# Main.net
KiCad netlist of a schematic drawn in Altium Designer
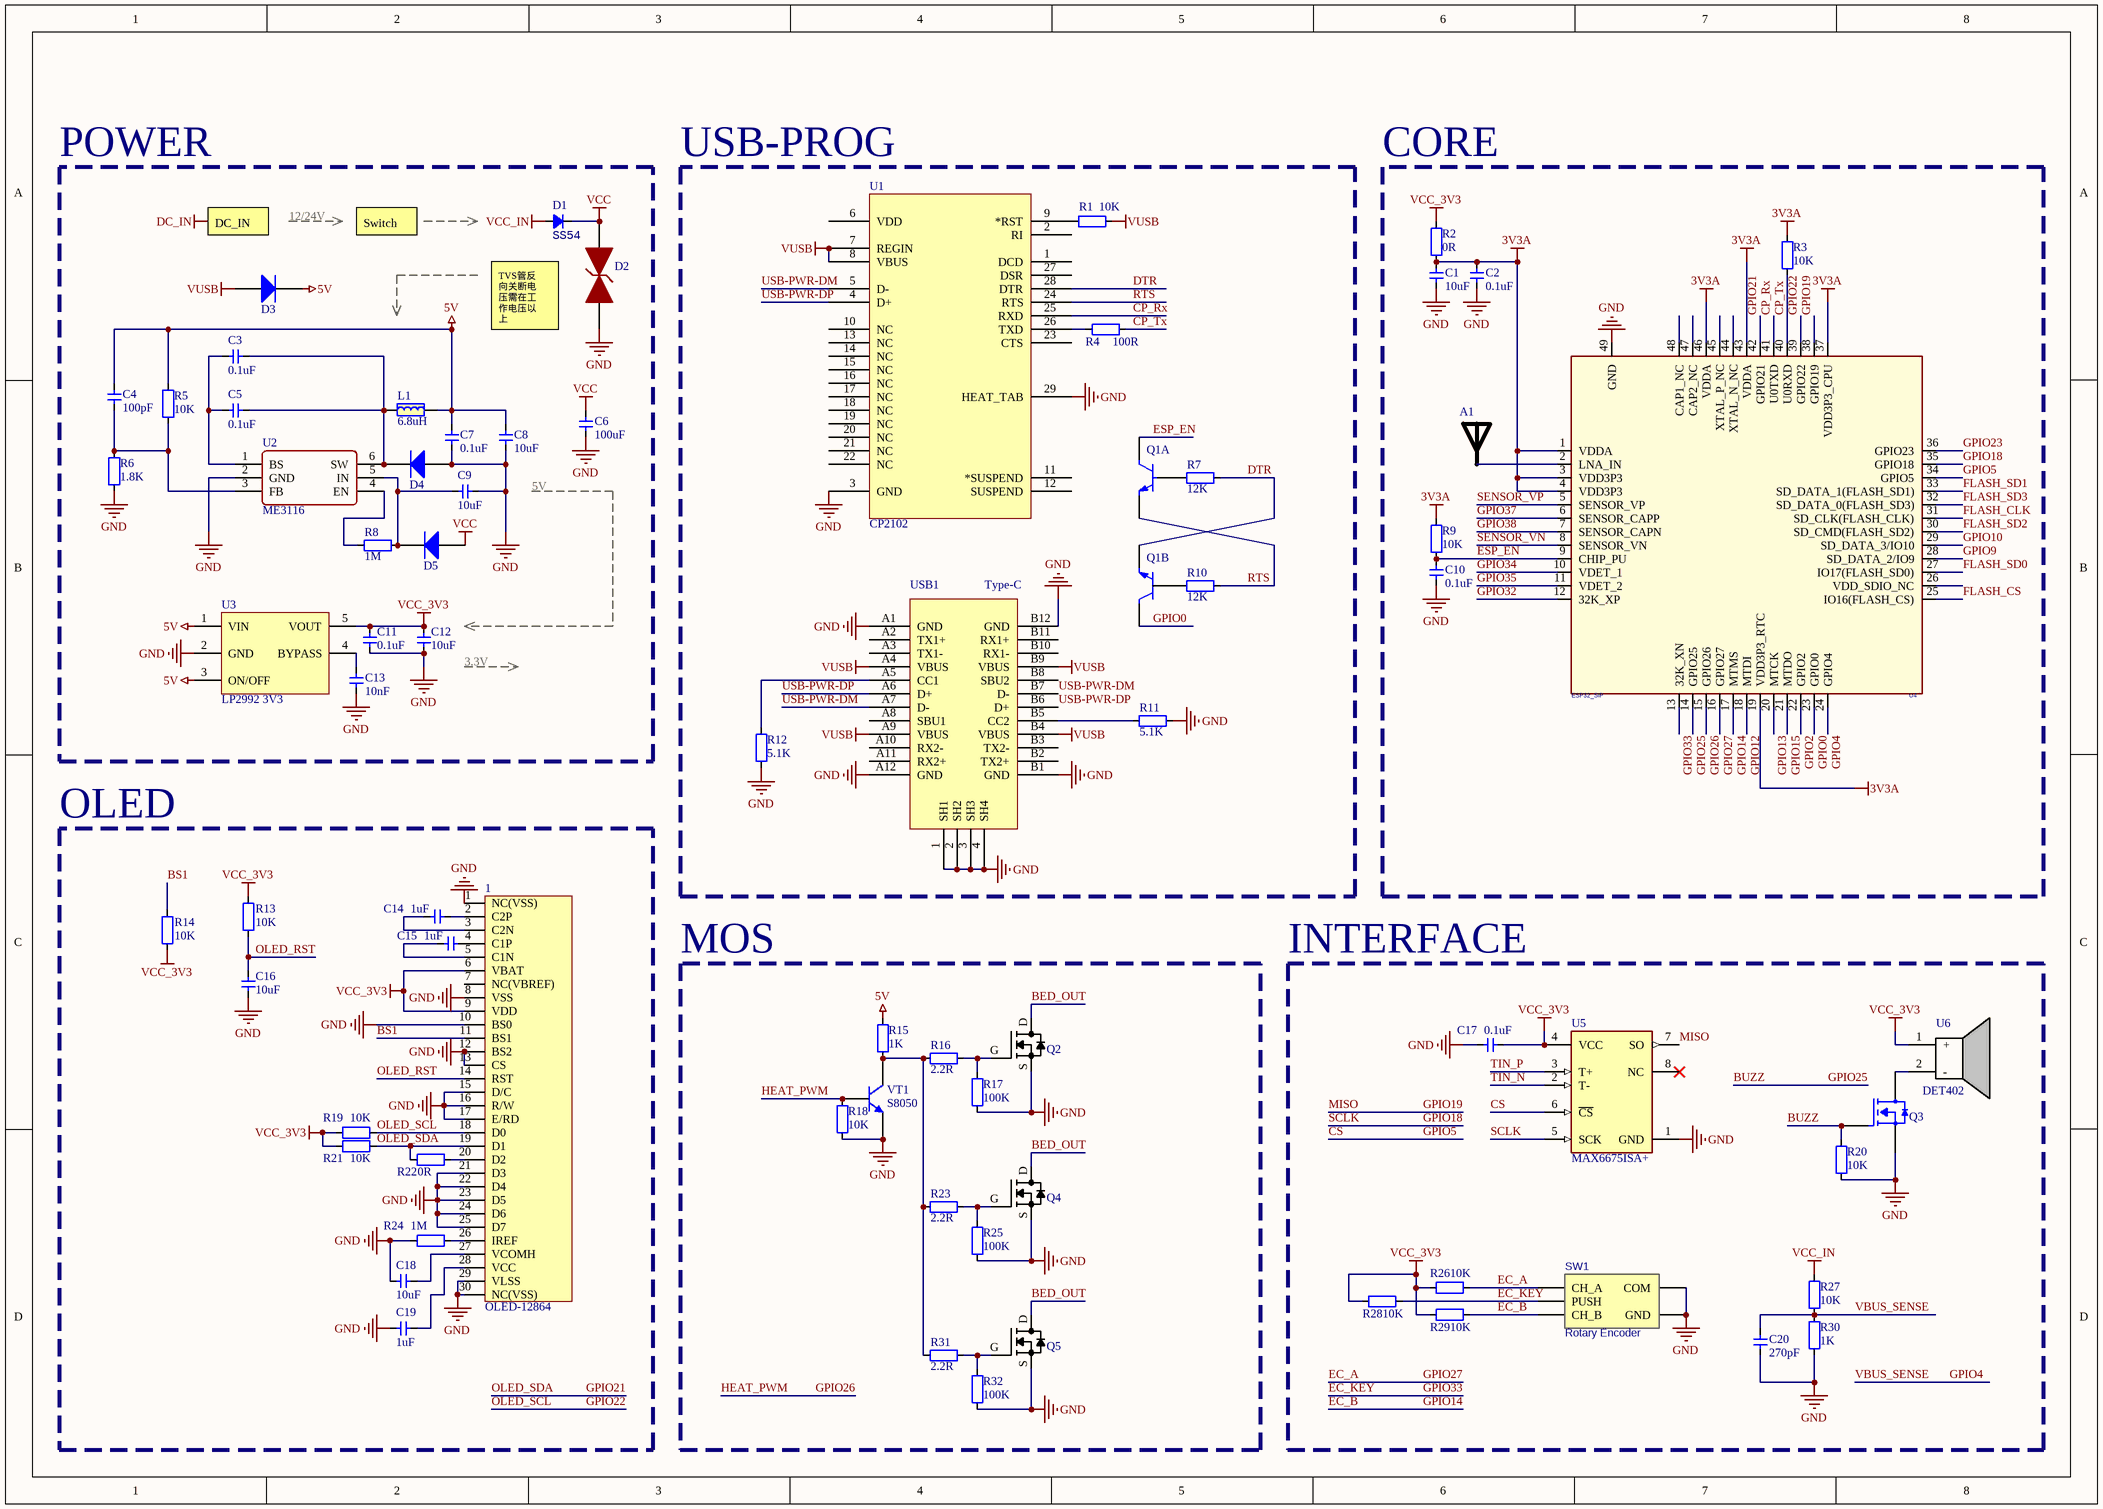
[diagram p0: Main.SchDoc]

(export (version "E")
  (design (tool "Eeschema 10.0.6"))
  (components
    (comp (ref "1")
      (value "OLED-12864")
      (footprint "OLED-12864-1.3-TOP")
      (description "显示屏")
      (libsource (lib "MyPcbLib") (part "OLED-12864"))
    )
    (comp (ref "A1")
      (value "RAINSUN")
      (footprint "ANT-Rainsun-AN5120")
      (libsource (lib "MyPcbLib") (part "ANT-Rainsun-AP5120"))
    )
    (comp (ref "C1")
      (value "10uF")
      (footprint "CAP_0402")
      (description "Capacitor")
      (libsource (lib "MyPcbLib") (part "电容-0402"))
    )
    (comp (ref "C2")
      (value "0.1uF")
      (footprint "CAP_0402")
      (description "Capacitor")
      (libsource (lib "MyPcbLib") (part "电容-0402"))
    )
    (comp (ref "C3")
      (value "0.1uF")
      (footprint "CAP_0402")
      (description "Capacitor")
      (libsource (lib "MyPcbLib") (part "电容-0402"))
    )
    (comp (ref "C4")
      (value "100pF")
      (footprint "CAP_0402")
      (description "Capacitor")
      (libsource (lib "MyPcbLib") (part "电容-0402"))
    )
    (comp (ref "C5")
      (value "0.1uF")
      (footprint "CAP_0402")
      (description "Capacitor")
      (libsource (lib "MyPcbLib") (part "电容-0402"))
    )
    (comp (ref "C6")
      (value "100uF")
      (footprint "1206-CAP")
      (description "Capacitor")
      (libsource (lib "MyPcbLib") (part "电容-1206"))
    )
    (comp (ref "C7")
      (value "0.1uF")
      (footprint "CAP_0402")
      (description "Capacitor")
      (libsource (lib "MyPcbLib") (part "电容-0402"))
    )
    (comp (ref "C8")
      (value "10uF")
      (footprint "CAP_0402")
      (description "Capacitor")
      (libsource (lib "MyPcbLib") (part "电容-0402"))
    )
    (comp (ref "C9")
      (value "10uF")
      (footprint "CAP_0402")
      (description "Capacitor")
      (libsource (lib "MyPcbLib") (part "电容-0402"))
    )
    (comp (ref "C10")
      (value "0.1uF")
      (footprint "CAP_0402")
      (description "Capacitor")
      (libsource (lib "MyPcbLib") (part "电容-0402"))
    )
    (comp (ref "C11")
      (value "0.1uF")
      (footprint "CAP_0402")
      (description "Capacitor")
      (libsource (lib "MyPcbLib") (part "电容-0402"))
    )
    (comp (ref "C12")
      (value "10uF")
      (footprint "CAP_0402")
      (description "Capacitor")
      (libsource (lib "MyPcbLib") (part "电容-0402"))
    )
    (comp (ref "C13")
      (value "10nF")
      (footprint "CAP_0402")
      (description "Capacitor")
      (libsource (lib "MyPcbLib") (part "电容-0402"))
    )
    (comp (ref "C14")
      (value "1uF")
      (footprint "CAP_0402")
      (description "Capacitor")
      (libsource (lib "MyPcbLib") (part "电容-0402"))
    )
    (comp (ref "C15")
      (value "1uF")
      (footprint "CAP_0402")
      (description "Capacitor")
      (libsource (lib "MyPcbLib") (part "电容-0402"))
    )
    (comp (ref "C16")
      (value "10uF")
      (footprint "CAP_0402")
      (description "Capacitor")
      (libsource (lib "MyPcbLib") (part "电容-0402"))
    )
    (comp (ref "C17")
      (value "0.1uF")
      (footprint "CAP_0402")
      (description "Capacitor")
      (libsource (lib "MyPcbLib") (part "电容-0402"))
    )
    (comp (ref "C18")
      (value "10uF")
      (footprint "CAP_0402")
      (description "Capacitor")
      (libsource (lib "MyPcbLib") (part "电容-0402"))
    )
    (comp (ref "C19")
      (value "1uF")
      (footprint "CAP_0402")
      (description "Capacitor")
      (libsource (lib "MyPcbLib") (part "电容-0402"))
    )
    (comp (ref "C20")
      (value "270pF")
      (footprint "CAP_0402")
      (description "Capacitor")
      (libsource (lib "MyPcbLib") (part "电容-0402"))
    )
    (comp (ref "D1")
      (value "SS54")
      (footprint "DO-214AC")
      (description "Diode")
      (libsource (lib "KitSprout") (part "Diode_SMA"))
    )
    (comp (ref "D2")
      (value "SMBJ28CA")
      (footprint "SMBJ-CA_MFG")
      (libsource (lib "MyPcbLib") (part "SMBJ28CA"))
    )
    (comp (ref "D3")
      (value "二极管-5819W")
      (footprint "SOD-323")
      (description "40V")
      (libsource (lib "MyPcbLib") (part "二极管-5819W"))
    )
    (comp (ref "D4")
      (value "二极管-5819W")
      (footprint "SOD-323")
      (description "40V")
      (libsource (lib "MyPcbLib") (part "二极管-5819W"))
    )
    (comp (ref "D5")
      (value "二极管-5819W")
      (footprint "SOD-323")
      (description "40V")
      (libsource (lib "MyPcbLib") (part "二极管-5819W"))
    )
    (comp (ref "L1") (value "6.8uH") (footprint "IND-201612") (libsource (lib "MyPcbLib") (part "电感-201612")))
    (comp (ref "Q1")
      (value "BC847BVC-7")
      (footprint "SOT563-6")
      (libsource (lib "MyPcbLib") (part "BC847BVC-7"))
    )
    (comp (ref "Q2")
      (value "NTMFS5C628NLT")
      (footprint "SO8FL")
      (description "MOSFET N-CH 60V SO8FL")
      (fields
        (field (name "MANUFACTURER") "ON Semiconductor")
        (field (name "MANUFACTURER PART NUMBER") "NTMFS5C628NLT1G")
      )
      (libsource (lib "MyPcbLib") (part "NTMFS5C628NLT"))
    )
    (comp (ref "Q3")
      (value "AO3400A")
      (footprint "SOT23-3")
      (description "N-MOS")
      (libsource (lib "MyPcbLib") (part "AO3400A"))
    )
    (comp (ref "Q4")
      (value "NTMFS5C628NLT")
      (footprint "SO8FL")
      (description "MOSFET N-CH 60V SO8FL")
      (fields
        (field (name "MANUFACTURER") "ON Semiconductor")
        (field (name "MANUFACTURER PART NUMBER") "NTMFS5C628NLT1G")
      )
      (libsource (lib "MyPcbLib") (part "NTMFS5C628NLT"))
    )
    (comp (ref "Q5")
      (value "NTMFS5C628NLT")
      (footprint "SO8FL")
      (description "MOSFET N-CH 60V SO8FL")
      (fields
        (field (name "MANUFACTURER") "ON Semiconductor")
        (field (name "MANUFACTURER PART NUMBER") "NTMFS5C628NLT1G")
      )
      (libsource (lib "MyPcbLib") (part "NTMFS5C628NLT"))
    )
    (comp (ref "R1")
      (value "10K")
      (footprint "RES_0402")
      (description "Resistor")
      (libsource (lib "MyPcbLib") (part "电阻-0402"))
    )
    (comp (ref "R2")
      (value "0R")
      (footprint "RES_0402")
      (description "Resistor")
      (libsource (lib "") (part "电阻-0402_1"))
    )
    (comp (ref "R3")
      (value "10K")
      (footprint "RES_0402")
      (description "Resistor")
      (libsource (lib "") (part "电阻-0402_2"))
    )
    (comp (ref "R4")
      (value "100R")
      (footprint "RES_0402")
      (description "Resistor")
      (libsource (lib "MyPcbLib") (part "电阻-0402"))
    )
    (comp (ref "R5")
      (value "10K")
      (footprint "RES_0402")
      (description "Resistor")
      (libsource (lib "") (part "电阻-0402_2"))
    )
    (comp (ref "R6")
      (value "1.8K")
      (footprint "RES_0402")
      (description "Resistor")
      (libsource (lib "") (part "电阻-0402_2"))
    )
    (comp (ref "R7")
      (value "12K")
      (footprint "RES_0402")
      (description "Resistor")
      (libsource (lib "MyPcbLib") (part "电阻-0402"))
    )
    (comp (ref "R8")
      (value "1M")
      (footprint "RES_0402")
      (description "Resistor")
      (libsource (lib "MyPcbLib") (part "电阻-0402"))
    )
    (comp (ref "R9")
      (value "10K")
      (footprint "RES_0402")
      (description "Resistor")
      (libsource (lib "") (part "电阻-0402_1"))
    )
    (comp (ref "R10")
      (value "12K")
      (footprint "RES_0402")
      (description "Resistor")
      (libsource (lib "MyPcbLib") (part "电阻-0402"))
    )
    (comp (ref "R11")
      (value "5.1K")
      (footprint "RES_0402")
      (description "Resistor")
      (libsource (lib "MyPcbLib") (part "电阻-0402"))
    )
    (comp (ref "R12")
      (value "5.1K")
      (footprint "RES_0402")
      (description "Resistor")
      (libsource (lib "") (part "电阻-0402_1"))
    )
    (comp (ref "R13")
      (value "10K")
      (footprint "RES_0402")
      (description "Resistor")
      (libsource (lib "") (part "电阻-0402_2"))
    )
    (comp (ref "R14")
      (value "10K")
      (footprint "RES_0402")
      (description "Resistor")
      (libsource (lib "") (part "电阻-0402_2"))
    )
    (comp (ref "R15")
      (value "1K")
      (footprint "RES_0402")
      (description "Resistor")
      (libsource (lib "") (part "电阻-0402_2"))
    )
    (comp (ref "R16")
      (value "2.2R")
      (footprint "RES_0402")
      (description "Resistor")
      (libsource (lib "MyPcbLib") (part "电阻-0402"))
    )
    (comp (ref "R17")
      (value "100K")
      (footprint "RES_0402")
      (description "Resistor")
      (libsource (lib "") (part "电阻-0402_1"))
    )
    (comp (ref "R18")
      (value "10K")
      (footprint "RES_0402")
      (description "Resistor")
      (libsource (lib "") (part "电阻-0402_1"))
    )
    (comp (ref "R19")
      (value "10K")
      (footprint "RES_0402")
      (description "Resistor")
      (libsource (lib "") (part "电阻-0402_3"))
    )
    (comp (ref "R20")
      (value "10K")
      (footprint "RES_0402")
      (description "Resistor")
      (libsource (lib "") (part "电阻-0402_2"))
    )
    (comp (ref "R21")
      (value "10K")
      (footprint "RES_0402")
      (description "Resistor")
      (libsource (lib "") (part "电阻-0402_3"))
    )
    (comp (ref "R22")
      (value "0R")
      (footprint "RES_0402")
      (description "Resistor")
      (libsource (lib "MyPcbLib") (part "电阻-0402"))
    )
    (comp (ref "R23")
      (value "2.2R")
      (footprint "RES_0402")
      (description "Resistor")
      (libsource (lib "MyPcbLib") (part "电阻-0402"))
    )
    (comp (ref "R24")
      (value "1M")
      (footprint "RES_0402")
      (description "Resistor")
      (libsource (lib "") (part "电阻-0402_3"))
    )
    (comp (ref "R25")
      (value "100K")
      (footprint "RES_0402")
      (description "Resistor")
      (libsource (lib "") (part "电阻-0402_1"))
    )
    (comp (ref "R26")
      (value "10K")
      (footprint "RES_0402")
      (description "Resistor")
      (libsource (lib "MyPcbLib") (part "电阻-0402"))
    )
    (comp (ref "R27")
      (value "10K")
      (footprint "RES_0402")
      (description "Resistor")
      (libsource (lib "") (part "电阻-0402_1"))
    )
    (comp (ref "R28")
      (value "10K")
      (footprint "RES_0402")
      (description "Resistor")
      (libsource (lib "MyPcbLib") (part "电阻-0402"))
    )
    (comp (ref "R29")
      (value "10K")
      (footprint "RES_0402")
      (description "Resistor")
      (libsource (lib "MyPcbLib") (part "电阻-0402"))
    )
    (comp (ref "R30")
      (value "1K")
      (footprint "RES_0402")
      (description "Resistor")
      (libsource (lib "") (part "电阻-0402_1"))
    )
    (comp (ref "R31")
      (value "2.2R")
      (footprint "RES_0402")
      (description "Resistor")
      (libsource (lib "MyPcbLib") (part "电阻-0402"))
    )
    (comp (ref "R32")
      (value "100K")
      (footprint "RES_0402")
      (description "Resistor")
      (libsource (lib "") (part "电阻-0402_1"))
    )
    (comp (ref "SW1")
      (value "Rotary Encoder")
      (footprint "SIQ-02FVS3")
      (fields
        (field (name "BOM_SUPPLIER PART") "C1322543")
        (field (name "BOM_MANUFACTURER PART") "EC11E1534443")
        (field (name "CONTRIBUTOR") "LCSC")
      )
      (libsource (lib "MyPcbLib") (part "Rotary Encoder"))
    )
    (comp (ref "U1")
      (value "CP2102")
      (footprint "QFN-28")
      (description "USB转TTL")
      (libsource (lib "mLib") (part "CP2102"))
    )
    (comp (ref "U2")
      (value "ME3116")
      (footprint "SOT23-6")
      (description "DC-DC")
      (libsource (lib "MyPcbLib") (part "ME3116"))
    )
    (comp (ref "U3")
      (value "LP2992 3V3")
      (footprint "SOT23-5")
      (description "LDO")
      (libsource (lib "mLib") (part "LP2992"))
    )
    (comp (ref "U4")
      (value "ESP32_SIP")
      (footprint "QFN-48_7X7")
      (libsource (lib "mLib") (part "ESP32-PICO"))
    )
    (comp (ref "U5")
      (value "MAX6675ISA")
      (footprint "SO-8")
      (description "IC THERMOCOUP TO DGTL 8-SOIC")
      (fields
        (field (name "MANUFACTURER") "Maxim Electronics")
        (field (name "OCTOPART PART NUMBER") "33bcfab92ad8ec7b")
        (field (name "PART NUMBER") "MAX6675ISA+")
      )
      (libsource (lib "MyPcbLib") (part "MAX6675ISA"))
    )
    (comp (ref "U6") (value "DET402") (footprint "DET402") (libsource (lib "MyPcbLib") (part "DET402")))
    (comp (ref "USB1")
      (value "Type-C")
      (footprint "Type-C-TOP")
      (libsource (lib "MyPcbLib") (part "USB-Type-C-TOP"))
    )
    (comp (ref "VT1")
      (value "S8050")
      (footprint "SMT_TRIODE_NPN")
      (description "Surface mount NPN transistor, package SOT-23")
      (libsource (lib "MyPcbLib") (part "SMT_TRIODE_NPN"))
    )
  )
  (nets
    (net (code "1") (name "/BED_OUT") (class "Default")
      (node (ref "Q2") (pin "D") (pinfunction "D_D") (pintype "passive"))
      (node (ref "Q4") (pin "D") (pinfunction "D_D") (pintype "passive"))
      (node (ref "Q5") (pin "D") (pinfunction "D_D") (pintype "passive"))
    )
    (net (code "2") (name "/BS1") (class "Default")
      (node (ref "1") (pin "11") (pinfunction "BS1_11") (pintype "passive"))
      (node (ref "R14") (pin "2") (pinfunction "2_2") (pintype "passive"))
    )
    (net (code "3") (name "/BUZZ") (class "Default")
      (node (ref "Q3") (pin "1") (pinfunction "G_1") (pintype "passive"))
      (node (ref "R20") (pin "2") (pinfunction "2_2") (pintype "passive"))
      (node (ref "U4") (pin "14") (pinfunction "GPIO25_14") (pintype "passive"))
    )
    (net (code "4") (name "/CP_Rx") (class "Default")
      (node (ref "U1") (pin "25") (pinfunction "RXD_25") (pintype "passive"))
      (node (ref "U4") (pin "41") (pinfunction "U0TXD_41") (pintype "power_in"))
    )
    (net (code "5") (name "/CP_Tx") (class "Default")
      (node (ref "R3") (pin "1") (pinfunction "1_1") (pintype "passive"))
      (node (ref "R4") (pin "1") (pinfunction "1_1") (pintype "passive"))
      (node (ref "U4") (pin "40") (pinfunction "U0RXD_40") (pintype "power_in"))
    )
    (net (code "6") (name "/CS") (class "Default")
      (node (ref "U4") (pin "34") (pinfunction "GPIO5_34") (pintype "passive"))
      (node (ref "U5") (pin "6") (pinfunction "~{CS}_6") (pintype "input"))
    )
    (net (code "7") (name "/DTR") (class "Default")
      (node (ref "Q1") (pin "4") (pinfunction "E2_4") (pintype "passive"))
      (node (ref "R7") (pin "1") (pinfunction "1_1") (pintype "passive"))
      (node (ref "U1") (pin "28") (pinfunction "DTR_28") (pintype "passive"))
    )
    (net (code "8") (name "/EC_A") (class "Default")
      (node (ref "R26") (pin "1") (pinfunction "1_1") (pintype "passive"))
      (node (ref "SW1") (pin "1") (pinfunction "CH_A_1") (pintype "passive"))
      (node (ref "U4") (pin "16") (pinfunction "GPIO27_16") (pintype "passive"))
    )
    (net (code "9") (name "/EC_B") (class "Default")
      (node (ref "R29") (pin "1") (pinfunction "1_1") (pintype "passive"))
      (node (ref "SW1") (pin "4") (pinfunction "CH_B_4") (pintype "passive"))
      (node (ref "U4") (pin "17") (pinfunction "MTMS_17") (pintype "passive"))
    )
    (net (code "10") (name "/EC_KEY") (class "Default")
      (node (ref "R28") (pin "1") (pinfunction "1_1") (pintype "passive"))
      (node (ref "SW1") (pin "2") (pinfunction "PUSH_2") (pintype "passive"))
      (node (ref "U4") (pin "13") (pinfunction "32K_XN_13") (pintype "passive"))
    )
    (net (code "11") (name "/ESP_EN") (class "Default")
      (node (ref "C10") (pin "1") (pinfunction "1_1") (pintype "passive"))
      (node (ref "Q1") (pin "6") (pinfunction "C1_6") (pintype "passive"))
      (node (ref "R9") (pin "2") (pinfunction "2_2") (pintype "passive"))
      (node (ref "U4") (pin "9") (pinfunction "CHIP_PU_9") (pintype "passive"))
    )
    (net (code "12") (name "/FLASH_CLK") (class "Default")
      (node (ref "U4") (pin "31") (pinfunction "SD_CLK(FLASH_CLK)_31") (pintype "passive"))
    )
    (net (code "13") (name "/FLASH_CS") (class "Default")
      (node (ref "U4") (pin "25") (pinfunction "IO16(FLASH_CS)_25") (pintype "passive"))
    )
    (net (code "14") (name "/FLASH_SD0") (class "Default")
      (node (ref "U4") (pin "27") (pinfunction "IO17(FLASH_SD0)_27") (pintype "passive"))
    )
    (net (code "15") (name "/FLASH_SD1") (class "Default")
      (node (ref "U4") (pin "33") (pinfunction "SD_DATA_1(FLASH_SD1)_33") (pintype "passive"))
    )
    (net (code "16") (name "/FLASH_SD2") (class "Default")
      (node (ref "U4") (pin "30") (pinfunction "SD_CMD(FLASH_SD2)_30") (pintype "passive"))
    )
    (net (code "17") (name "/FLASH_SD3") (class "Default")
      (node (ref "U4") (pin "32") (pinfunction "SD_DATA_0(FLASH_SD3)_32") (pintype "passive"))
    )
    (net (code "18") (name "/GPIO0") (class "Default")
      (node (ref "Q1") (pin "3") (pinfunction "C2_3") (pintype "passive"))
      (node (ref "U4") (pin "23") (pinfunction "GPIO0_23") (pintype "passive"))
    )
    (net (code "19") (name "/GPIO2") (class "Default")
      (node (ref "U4") (pin "22") (pinfunction "GPIO2_22") (pintype "passive"))
    )
    (net (code "20") (name "/GPIO4") (class "Default")
      (node (ref "C20") (pin "2") (pinfunction "2_2") (pintype "passive"))
      (node (ref "R27") (pin "2") (pinfunction "2_2") (pintype "passive"))
      (node (ref "R30") (pin "1") (pinfunction "1_1") (pintype "passive"))
      (node (ref "U4") (pin "24") (pinfunction "GPIO4_24") (pintype "passive"))
    )
    (net (code "21") (name "/GPIO9") (class "Default")
      (node (ref "U4") (pin "28") (pinfunction "SD_DATA_2/IO9_28") (pintype "passive"))
    )
    (net (code "22") (name "/GPIO10") (class "Default")
      (node (ref "U4") (pin "29") (pinfunction "SD_DATA_3/IO10_29") (pintype "passive"))
    )
    (net (code "23") (name "/GPIO12") (class "Default")
      (node (ref "U4") (pin "18") (pinfunction "MTDI_18") (pintype "passive"))
    )
    (net (code "24") (name "/GPIO13") (class "Default")
      (node (ref "U4") (pin "20") (pinfunction "MTCK_20") (pintype "passive"))
    )
    (net (code "25") (name "/GPIO15") (class "Default")
      (node (ref "U4") (pin "21") (pinfunction "MTDO_21") (pintype "passive"))
    )
    (net (code "26") (name "/GPIO18") (class "Default")
      (node (ref "U4") (pin "35") (pinfunction "GPIO18_35") (pintype "passive"))
      (node (ref "U5") (pin "5") (pinfunction "SCK_5") (pintype "input"))
    )
    (net (code "27") (name "/GPIO19") (class "Default")
      (node (ref "U4") (pin "38") (pinfunction "GPIO19_38") (pintype "passive"))
      (node (ref "U5") (pin "7") (pinfunction "SO_7") (pintype "output"))
    )
    (net (code "28") (name "/GPIO21") (class "Default")
      (node (ref "1") (pin "19") (pinfunction "D1_19") (pintype "passive"))
      (node (ref "R21") (pin "2") (pinfunction "2_2") (pintype "passive"))
      (node (ref "R22") (pin "2") (pinfunction "2_2") (pintype "passive"))
      (node (ref "U4") (pin "42") (pinfunction "GPIO21_42") (pintype "passive"))
    )
    (net (code "29") (name "/GPIO22") (class "Default")
      (node (ref "1") (pin "18") (pinfunction "D0_18") (pintype "passive"))
      (node (ref "R19") (pin "2") (pinfunction "2_2") (pintype "passive"))
      (node (ref "U4") (pin "39") (pinfunction "GPIO22_39") (pintype "passive"))
    )
    (net (code "30") (name "/GPIO23") (class "Default")
      (node (ref "U4") (pin "36") (pinfunction "GPIO23_36") (pintype "passive"))
    )
    (net (code "31") (name "/GPIO26") (class "Default")
      (node (ref "R18") (pin "1") (pinfunction "1_1") (pintype "passive"))
      (node (ref "U4") (pin "15") (pinfunction "GPIO26_15") (pintype "passive"))
      (node (ref "VT1") (pin "1") (pinfunction "B_1") (pintype "passive"))
    )
    (net (code "32") (name "/GPIO32") (class "Default")
      (node (ref "U4") (pin "12") (pinfunction "32K_XP_12") (pintype "passive"))
    )
    (net (code "33") (name "/GPIO34") (class "Default")
      (node (ref "U4") (pin "10") (pinfunction "VDET_1_10") (pintype "passive"))
    )
    (net (code "34") (name "/GPIO35") (class "Default")
      (node (ref "U4") (pin "11") (pinfunction "VDET_2_11") (pintype "passive"))
    )
    (net (code "35") (name "/GPIO37") (class "Default")
      (node (ref "U4") (pin "6") (pinfunction "SENSOR_CAPP_6") (pintype "passive"))
    )
    (net (code "36") (name "/GPIO38") (class "Default")
      (node (ref "U4") (pin "7") (pinfunction "SENSOR_CAPN_7") (pintype "passive"))
    )
    (net (code "37") (name "/OLED_RST") (class "Default")
      (node (ref "1") (pin "14") (pinfunction "RST_14") (pintype "passive"))
      (node (ref "C16") (pin "2") (pinfunction "2_2") (pintype "passive"))
      (node (ref "R13") (pin "1") (pinfunction "1_1") (pintype "passive"))
    )
    (net (code "38") (name "/RTS") (class "Default")
      (node (ref "Q1") (pin "1") (pinfunction "E1_1") (pintype "passive"))
      (node (ref "R10") (pin "1") (pinfunction "1_1") (pintype "passive"))
      (node (ref "U1") (pin "24") (pinfunction "RTS_24") (pintype "passive"))
    )
    (net (code "39") (name "/SENSOR_VN") (class "Default")
      (node (ref "U4") (pin "8") (pinfunction "SENSOR_VN_8") (pintype "passive"))
    )
    (net (code "40") (name "/SENSOR_VP") (class "Default")
      (node (ref "U4") (pin "5") (pinfunction "SENSOR_VP_5") (pintype "passive"))
    )
    (net (code "41") (name "/TIN_N") (class "Default")
      (node (ref "U5") (pin "2") (pinfunction "T-_2") (pintype "input"))
    )
    (net (code "42") (name "/TIN_P") (class "Default")
      (node (ref "U5") (pin "3") (pinfunction "T+_3") (pintype "input"))
    )
    (net (code "43") (name "/USB-PWR-DM") (class "Default")
      (node (ref "U1") (pin "5") (pinfunction "D-_5") (pintype "passive"))
      (node (ref "USB1") (pin "A7") (pinfunction "D-_A7") (pintype "passive"))
      (node (ref "USB1") (pin "B7") (pinfunction "D-_B7") (pintype "passive"))
    )
    (net (code "44") (name "/USB-PWR-DP") (class "Default")
      (node (ref "U1") (pin "4") (pinfunction "D+_4") (pintype "passive"))
      (node (ref "USB1") (pin "A6") (pinfunction "D+_A6") (pintype "passive"))
      (node (ref "USB1") (pin "B6") (pinfunction "D+_B6") (pintype "passive"))
    )
    (net (code "45") (name "3V3A") (class "Default")
      (node (ref "C1") (pin "2") (pinfunction "2_2") (pintype "passive"))
      (node (ref "C2") (pin "2") (pinfunction "2_2") (pintype "passive"))
      (node (ref "R2") (pin "2") (pinfunction "2_2") (pintype "passive"))
      (node (ref "R3") (pin "2") (pinfunction "2_2") (pintype "passive"))
      (node (ref "R9") (pin "1") (pinfunction "1_1") (pintype "passive"))
      (node (ref "U4") (pin "1") (pinfunction "VDDA_1") (pintype "power_in"))
      (node (ref "U4") (pin "19") (pinfunction "VDD3P3_RTC_19") (pintype "power_in"))
      (node (ref "U4") (pin "3") (pinfunction "VDD3P3_3") (pintype "power_in"))
      (node (ref "U4") (pin "37") (pinfunction "VDD3P3_CPU_37") (pintype "power_in"))
      (node (ref "U4") (pin "4") (pinfunction "VDD3P3_4") (pintype "power_in"))
      (node (ref "U4") (pin "43") (pinfunction "VDDA_43") (pintype "power_in"))
      (node (ref "U4") (pin "46") (pinfunction "VDDA_46") (pintype "power_in"))
    )
    (net (code "46") (name "5V") (class "Default")
      (node (ref "C4") (pin "1") (pinfunction "1_1") (pintype "passive"))
      (node (ref "C7") (pin "2") (pinfunction "2_2") (pintype "passive"))
      (node (ref "C8") (pin "2") (pinfunction "2_2") (pintype "passive"))
      (node (ref "D3") (pin "2") (pinfunction "K_2") (pintype "passive"))
      (node (ref "L1") (pin "2") (pinfunction "2_2") (pintype "passive"))
      (node (ref "R15") (pin "2") (pinfunction "2_2") (pintype "passive"))
      (node (ref "R5") (pin "2") (pinfunction "2_2") (pintype "passive"))
      (node (ref "U3") (pin "1") (pinfunction "VIN_1") (pintype "passive"))
      (node (ref "U3") (pin "3") (pinfunction "ON/OFF_3") (pintype "passive"))
    )
    (net (code "48") (name "GND") (class "Default")
      (node (ref "1") (pin "1") (pinfunction "NC(VSS)_1") (pintype "passive"))
      (node (ref "1") (pin "10") (pinfunction "BS0_10") (pintype "passive"))
      (node (ref "1") (pin "12") (pinfunction "BS2_12") (pintype "passive"))
      (node (ref "1") (pin "13") (pinfunction "CS_13") (pintype "passive"))
      (node (ref "1") (pin "15") (pinfunction "D/C_15") (pintype "passive"))
      (node (ref "1") (pin "16") (pinfunction "R/W_16") (pintype "passive"))
      (node (ref "1") (pin "17") (pinfunction "E/RD_17") (pintype "passive"))
      (node (ref "1") (pin "21") (pinfunction "D3_21") (pintype "passive"))
      (node (ref "1") (pin "22") (pinfunction "D4_22") (pintype "passive"))
      (node (ref "1") (pin "23") (pinfunction "D5_23") (pintype "passive"))
      (node (ref "1") (pin "24") (pinfunction "D6_24") (pintype "passive"))
      (node (ref "1") (pin "25") (pinfunction "D7_25") (pintype "passive"))
      (node (ref "1") (pin "29") (pinfunction "VLSS_29") (pintype "passive"))
      (node (ref "1") (pin "30") (pinfunction "NC(VSS)_30") (pintype "passive"))
      (node (ref "1") (pin "8") (pinfunction "VSS_8") (pintype "passive"))
      (node (ref "C1") (pin "1") (pinfunction "1_1") (pintype "passive"))
      (node (ref "C10") (pin "2") (pinfunction "2_2") (pintype "passive"))
      (node (ref "C11") (pin "1") (pinfunction "1_1") (pintype "passive"))
      (node (ref "C12") (pin "1") (pinfunction "1_1") (pintype "passive"))
      (node (ref "C13") (pin "1") (pinfunction "1_1") (pintype "passive"))
      (node (ref "C16") (pin "1") (pinfunction "1_1") (pintype "passive"))
      (node (ref "C17") (pin "2") (pinfunction "2_2") (pintype "passive"))
      (node (ref "C18") (pin "2") (pinfunction "2_2") (pintype "passive"))
      (node (ref "C19") (pin "2") (pinfunction "2_2") (pintype "passive"))
      (node (ref "C2") (pin "1") (pinfunction "1_1") (pintype "passive"))
      (node (ref "C20") (pin "1") (pinfunction "1_1") (pintype "passive"))
      (node (ref "C6") (pin "1") (pinfunction "1_1") (pintype "passive"))
      (node (ref "C7") (pin "1") (pinfunction "1_1") (pintype "passive"))
      (node (ref "C8") (pin "1") (pinfunction "1_1") (pintype "passive"))
      (node (ref "C9") (pin "1") (pinfunction "1_1") (pintype "passive"))
      (node (ref "D2") (pin "1") (pinfunction "1_1") (pintype "passive"))
      (node (ref "D4") (pin "1") (pinfunction "A_1") (pintype "passive"))
      (node (ref "Q2") (pin "S") (pinfunction "S_S") (pintype "passive"))
      (node (ref "Q3") (pin "2") (pinfunction "S_2") (pintype "passive"))
      (node (ref "Q4") (pin "S") (pinfunction "S_S") (pintype "passive"))
      (node (ref "Q5") (pin "S") (pinfunction "S_S") (pintype "passive"))
      (node (ref "R11") (pin "1") (pinfunction "1_1") (pintype "passive"))
      (node (ref "R12") (pin "2") (pinfunction "2_2") (pintype "passive"))
      (node (ref "R17") (pin "2") (pinfunction "2_2") (pintype "passive"))
      (node (ref "R18") (pin "2") (pinfunction "2_2") (pintype "passive"))
      (node (ref "R20") (pin "1") (pinfunction "1_1") (pintype "passive"))
      (node (ref "R24") (pin "1") (pinfunction "1_1") (pintype "passive"))
      (node (ref "R25") (pin "2") (pinfunction "2_2") (pintype "passive"))
      (node (ref "R30") (pin "2") (pinfunction "2_2") (pintype "passive"))
      (node (ref "R32") (pin "2") (pinfunction "2_2") (pintype "passive"))
      (node (ref "R6") (pin "1") (pinfunction "1_1") (pintype "passive"))
      (node (ref "SW1") (pin "3") (pinfunction "COM_3") (pintype "passive"))
      (node (ref "SW1") (pin "5") (pinfunction "GND_5") (pintype "passive"))
      (node (ref "U1") (pin "29") (pinfunction "HEAT_TAB_29") (pintype "passive"))
      (node (ref "U1") (pin "3") (pinfunction "GND_3") (pintype "passive"))
      (node (ref "U2") (pin "2") (pinfunction "GND_2") (pintype "passive"))
      (node (ref "U3") (pin "2") (pinfunction "GND_2") (pintype "passive"))
      (node (ref "U4") (pin "49") (pinfunction "GND_49") (pintype "power_in"))
      (node (ref "U5") (pin "1") (pinfunction "GND_1") (pintype "power_in"))
      (node (ref "USB1") (pin "1") (pinfunction "SH1_1") (pintype "passive"))
      (node (ref "USB1") (pin "2") (pinfunction "SH2_2") (pintype "passive"))
      (node (ref "USB1") (pin "3") (pinfunction "SH3_3") (pintype "passive"))
      (node (ref "USB1") (pin "4") (pinfunction "SH4_4") (pintype "passive"))
      (node (ref "USB1") (pin "A1") (pinfunction "GND_A1") (pintype "passive"))
      (node (ref "USB1") (pin "A12") (pinfunction "GND_A12") (pintype "passive"))
      (node (ref "USB1") (pin "B1") (pinfunction "GND_B1") (pintype "passive"))
      (node (ref "USB1") (pin "B12") (pinfunction "GND_B12") (pintype "passive"))
      (node (ref "VT1") (pin "2") (pinfunction "E_2") (pintype "passive"))
    )
    (net (code "49") (name "Net-(1-C1N)") (class "Default")
      (node (ref "1") (pin "5") (pinfunction "C1N_5") (pintype "passive"))
      (node (ref "C15") (pin "2") (pinfunction "2_2") (pintype "passive"))
    )
    (net (code "50") (name "Net-(1-C1P)") (class "Default")
      (node (ref "1") (pin "4") (pinfunction "C1P_4") (pintype "passive"))
      (node (ref "C15") (pin "1") (pinfunction "1_1") (pintype "passive"))
    )
    (net (code "51") (name "Net-(1-C2N)") (class "Default")
      (node (ref "1") (pin "3") (pinfunction "C2N_3") (pintype "passive"))
      (node (ref "C14") (pin "2") (pinfunction "2_2") (pintype "passive"))
    )
    (net (code "52") (name "Net-(1-C2P)") (class "Default")
      (node (ref "1") (pin "2") (pinfunction "C2P_2") (pintype "passive"))
      (node (ref "C14") (pin "1") (pinfunction "1_1") (pintype "passive"))
    )
    (net (code "53") (name "Net-(1-D2)") (class "Default")
      (node (ref "1") (pin "20") (pinfunction "D2_20") (pintype "passive"))
      (node (ref "R22") (pin "1") (pinfunction "1_1") (pintype "passive"))
    )
    (net (code "54") (name "Net-(1-IREF)") (class "Default")
      (node (ref "1") (pin "26") (pinfunction "IREF_26") (pintype "passive"))
      (node (ref "R24") (pin "2") (pinfunction "2_2") (pintype "passive"))
    )
    (net (code "55") (name "Net-(1-VCC)") (class "Default")
      (node (ref "1") (pin "28") (pinfunction "VCC_28") (pintype "passive"))
      (node (ref "C19") (pin "1") (pinfunction "1_1") (pintype "passive"))
    )
    (net (code "56") (name "Net-(1-VCOMH)") (class "Default")
      (node (ref "1") (pin "27") (pinfunction "VCOMH_27") (pintype "passive"))
      (node (ref "C18") (pin "1") (pinfunction "1_1") (pintype "passive"))
    )
    (net (code "57") (name "Net-(D4-K)") (class "Default")
      (node (ref "C3") (pin "1") (pinfunction "1_1") (pintype "passive"))
      (node (ref "C5") (pin "1") (pinfunction "1_1") (pintype "passive"))
      (node (ref "D4") (pin "2") (pinfunction "K_2") (pintype "passive"))
      (node (ref "L1") (pin "1") (pintype "passive"))
      (node (ref "U2") (pin "6") (pinfunction "SW_6") (pintype "passive"))
    )
    (net (code "58") (name "Net-(D5-K)") (class "Default")
      (node (ref "C9") (pin "2") (pinfunction "2_2") (pintype "passive"))
      (node (ref "D5") (pin "2") (pinfunction "K_2") (pintype "passive"))
      (node (ref "R8") (pin "1") (pinfunction "1_1") (pintype "passive"))
      (node (ref "U2") (pin "5") (pinfunction "IN_5") (pintype "passive"))
    )
    (net (code "59") (name "Net-(Q1A-B1)") (class "Default")
      (node (ref "Q1") (pin "2") (pinfunction "B1_2") (pintype "passive"))
      (node (ref "R7") (pin "2") (pinfunction "2_2") (pintype "passive"))
    )
    (net (code "60") (name "Net-(Q1B-B2)") (class "Default")
      (node (ref "Q1") (pin "5") (pinfunction "B2_5") (pintype "passive"))
      (node (ref "R10") (pin "2") (pinfunction "2_2") (pintype "passive"))
    )
    (net (code "61") (name "Net-(Q2-PadG)") (class "Default")
      (node (ref "Q2") (pin "G") (pinfunction "G_G") (pintype "passive"))
      (node (ref "R16") (pin "1") (pinfunction "1_1") (pintype "passive"))
      (node (ref "R17") (pin "1") (pinfunction "1_1") (pintype "passive"))
    )
    (net (code "62") (name "Net-(Q3-D)") (class "Default")
      (node (ref "Q3") (pin "3") (pinfunction "D_3") (pintype "passive"))
      (node (ref "U6") (pin "2") (pinfunction "-_2") (pintype "passive"))
    )
    (net (code "63") (name "Net-(Q4-PadG)") (class "Default")
      (node (ref "Q4") (pin "G") (pinfunction "G_G") (pintype "passive"))
      (node (ref "R23") (pin "1") (pinfunction "1_1") (pintype "passive"))
      (node (ref "R25") (pin "1") (pinfunction "1_1") (pintype "passive"))
    )
    (net (code "64") (name "Net-(Q5-PadG)") (class "Default")
      (node (ref "Q5") (pin "G") (pinfunction "G_G") (pintype "passive"))
      (node (ref "R31") (pin "1") (pinfunction "1_1") (pintype "passive"))
      (node (ref "R32") (pin "1") (pinfunction "1_1") (pintype "passive"))
    )
    (net (code "65") (name "Net-(U1-*RST)") (class "Default")
      (node (ref "R1") (pin "2") (pinfunction "2_2") (pintype "passive"))
      (node (ref "U1") (pin "9") (pinfunction "*RST_9") (pintype "passive"))
    )
    (net (code "66") (name "Net-(U1-TXD)") (class "Default")
      (node (ref "R4") (pin "2") (pinfunction "2_2") (pintype "passive"))
      (node (ref "U1") (pin "26") (pinfunction "TXD_26") (pintype "passive"))
    )
    (net (code "67") (name "Net-(U2-BS)") (class "Default")
      (node (ref "C3") (pin "2") (pinfunction "2_2") (pintype "passive"))
      (node (ref "C5") (pin "2") (pinfunction "2_2") (pintype "passive"))
      (node (ref "U2") (pin "1") (pinfunction "BS_1") (pintype "passive"))
    )
    (net (code "68") (name "Net-(U2-EN)") (class "Default")
      (node (ref "R8") (pin "2") (pinfunction "2_2") (pintype "passive"))
      (node (ref "U2") (pin "4") (pinfunction "EN_4") (pintype "passive"))
    )
    (net (code "69") (name "Net-(U2-FB)") (class "Default")
      (node (ref "C4") (pin "2") (pinfunction "2_2") (pintype "passive"))
      (node (ref "R5") (pin "1") (pinfunction "1_1") (pintype "passive"))
      (node (ref "R6") (pin "2") (pinfunction "2_2") (pintype "passive"))
      (node (ref "U2") (pin "3") (pinfunction "FB_3") (pintype "passive"))
    )
    (net (code "70") (name "Net-(U3-BYPASS)") (class "Default")
      (node (ref "C13") (pin "2") (pinfunction "2_2") (pintype "passive"))
      (node (ref "U3") (pin "4") (pinfunction "BYPASS_4") (pintype "passive"))
    )
    (net (code "71") (name "Net-(U4-LNA_IN)") (class "Default")
      (node (ref "A1") (pin "1") (pinfunction "1_1") (pintype "passive"))
      (node (ref "U4") (pin "2") (pinfunction "LNA_IN_2") (pintype "passive"))
    )
    (net (code "72") (name "Net-(USB1-CC1)") (class "Default")
      (node (ref "R12") (pin "1") (pinfunction "1_1") (pintype "passive"))
      (node (ref "USB1") (pin "A5") (pinfunction "CC1_A5") (pintype "passive"))
    )
    (net (code "73") (name "Net-(USB1-CC2)") (class "Default")
      (node (ref "R11") (pin "2") (pinfunction "2_2") (pintype "passive"))
      (node (ref "USB1") (pin "B5") (pinfunction "CC2_B5") (pintype "passive"))
    )
    (net (code "74") (name "Net-(VT1-C)") (class "Default")
      (node (ref "R15") (pin "1") (pinfunction "1_1") (pintype "passive"))
      (node (ref "R16") (pin "2") (pinfunction "2_2") (pintype "passive"))
      (node (ref "R23") (pin "2") (pinfunction "2_2") (pintype "passive"))
      (node (ref "R31") (pin "2") (pinfunction "2_2") (pintype "passive"))
      (node (ref "VT1") (pin "3") (pinfunction "C_3") (pintype "passive"))
    )
    (net (code "75") (name "VCC") (class "Default")
      (node (ref "C6") (pin "2") (pinfunction "2_2") (pintype "passive"))
      (node (ref "D1") (pin "2") (pinfunction "K_2") (pintype "passive"))
      (node (ref "D2") (pin "2") (pinfunction "2_2") (pintype "passive"))
      (node (ref "D5") (pin "1") (pinfunction "A_1") (pintype "passive"))
    )
    (net (code "76") (name "VCC_3V3") (class "Default")
      (node (ref "1") (pin "6") (pinfunction "VBAT_6") (pintype "passive"))
      (node (ref "1") (pin "9") (pinfunction "VDD_9") (pintype "passive"))
      (node (ref "C11") (pin "2") (pinfunction "2_2") (pintype "passive"))
      (node (ref "C12") (pin "2") (pinfunction "2_2") (pintype "passive"))
      (node (ref "C17") (pin "1") (pinfunction "1_1") (pintype "passive"))
      (node (ref "R13") (pin "2") (pinfunction "2_2") (pintype "passive"))
      (node (ref "R14") (pin "1") (pinfunction "1_1") (pintype "passive"))
      (node (ref "R19") (pin "1") (pinfunction "1_1") (pintype "passive"))
      (node (ref "R2") (pin "1") (pinfunction "1_1") (pintype "passive"))
      (node (ref "R21") (pin "1") (pinfunction "1_1") (pintype "passive"))
      (node (ref "R26") (pin "2") (pinfunction "2_2") (pintype "passive"))
      (node (ref "R28") (pin "2") (pinfunction "2_2") (pintype "passive"))
      (node (ref "R29") (pin "2") (pinfunction "2_2") (pintype "passive"))
      (node (ref "U3") (pin "5") (pinfunction "VOUT_5") (pintype "passive"))
      (node (ref "U5") (pin "4") (pinfunction "VCC_4") (pintype "power_in"))
      (node (ref "U6") (pin "1") (pinfunction "+_1") (pintype "passive"))
    )
    (net (code "77") (name "VCC_IN") (class "Default")
      (node (ref "D1") (pin "1") (pinfunction "A_1") (pintype "passive"))
      (node (ref "R27") (pin "1") (pinfunction "1_1") (pintype "passive"))
    )
    (net (code "78") (name "VUSB") (class "Default")
      (node (ref "D3") (pin "1") (pinfunction "A_1") (pintype "passive"))
      (node (ref "R1") (pin "1") (pinfunction "1_1") (pintype "passive"))
      (node (ref "U1") (pin "7") (pinfunction "REGIN_7") (pintype "passive"))
      (node (ref "U1") (pin "8") (pinfunction "VBUS_8") (pintype "passive"))
      (node (ref "USB1") (pin "A4") (pinfunction "VBUS_A4") (pintype "passive"))
      (node (ref "USB1") (pin "A9") (pinfunction "VBUS_A9") (pintype "passive"))
      (node (ref "USB1") (pin "B4") (pinfunction "VBUS_B4") (pintype "passive"))
      (node (ref "USB1") (pin "B9") (pinfunction "VBUS_B9") (pintype "passive"))
    )
    (net (code "79") (name "unconnected-(1-NC(VBREF)-Pad7)") (class "Default")
      (node (ref "1") (pin "7") (pinfunction "NC(VBREF)_7") (pintype "passive"))
    )
    (net (code "80") (name "unconnected-(U1-*SUSPEND-Pad11)") (class "Default")
      (node (ref "U1") (pin "11") (pinfunction "*SUSPEND_11") (pintype "passive"))
    )
    (net (code "81") (name "unconnected-(U1-CTS-Pad23)") (class "Default")
      (node (ref "U1") (pin "23") (pinfunction "CTS_23") (pintype "passive"))
    )
    (net (code "82") (name "unconnected-(U1-DCD-Pad1)") (class "Default")
      (node (ref "U1") (pin "1") (pinfunction "DCD_1") (pintype "passive"))
    )
    (net (code "83") (name "unconnected-(U1-DSR-Pad27)") (class "Default")
      (node (ref "U1") (pin "27") (pinfunction "DSR_27") (pintype "passive"))
    )
    (net (code "84") (name "unconnected-(U1-NC-Pad10)") (class "Default")
      (node (ref "U1") (pin "10") (pinfunction "NC_10") (pintype "passive"))
    )
    (net (code "85") (name "unconnected-(U1-NC-Pad13)") (class "Default")
      (node (ref "U1") (pin "13") (pinfunction "NC_13") (pintype "passive"))
    )
    (net (code "86") (name "unconnected-(U1-NC-Pad14)") (class "Default")
      (node (ref "U1") (pin "14") (pinfunction "NC_14") (pintype "passive"))
    )
    (net (code "87") (name "unconnected-(U1-NC-Pad15)") (class "Default")
      (node (ref "U1") (pin "15") (pinfunction "NC_15") (pintype "passive"))
    )
    (net (code "88") (name "unconnected-(U1-NC-Pad16)") (class "Default")
      (node (ref "U1") (pin "16") (pinfunction "NC_16") (pintype "passive"))
    )
    (net (code "89") (name "unconnected-(U1-NC-Pad17)") (class "Default")
      (node (ref "U1") (pin "17") (pinfunction "NC_17") (pintype "passive"))
    )
    (net (code "90") (name "unconnected-(U1-NC-Pad18)") (class "Default")
      (node (ref "U1") (pin "18") (pinfunction "NC_18") (pintype "passive"))
    )
    (net (code "91") (name "unconnected-(U1-NC-Pad19)") (class "Default")
      (node (ref "U1") (pin "19") (pinfunction "NC_19") (pintype "passive"))
    )
    (net (code "92") (name "unconnected-(U1-NC-Pad20)") (class "Default")
      (node (ref "U1") (pin "20") (pinfunction "NC_20") (pintype "passive"))
    )
    (net (code "93") (name "unconnected-(U1-NC-Pad21)") (class "Default")
      (node (ref "U1") (pin "21") (pinfunction "NC_21") (pintype "passive"))
    )
    (net (code "94") (name "unconnected-(U1-NC-Pad22)") (class "Default")
      (node (ref "U1") (pin "22") (pinfunction "NC_22") (pintype "passive"))
    )
    (net (code "95") (name "unconnected-(U1-RI-Pad2)") (class "Default")
      (node (ref "U1") (pin "2") (pinfunction "RI_2") (pintype "passive"))
    )
    (net (code "96") (name "unconnected-(U1-SUSPEND-Pad12)") (class "Default")
      (node (ref "U1") (pin "12") (pinfunction "SUSPEND_12") (pintype "passive"))
    )
    (net (code "97") (name "unconnected-(U1-VDD-Pad6)") (class "Default")
      (node (ref "U1") (pin "6") (pinfunction "VDD_6") (pintype "passive"))
    )
    (net (code "98") (name "unconnected-(U4-CAP1_NC-Pad48)") (class "Default")
      (node (ref "U4") (pin "48") (pinfunction "CAP1_NC_48") (pintype "passive"))
    )
    (net (code "99") (name "unconnected-(U4-CAP2_NC-Pad47)") (class "Default")
      (node (ref "U4") (pin "47") (pinfunction "CAP2_NC_47") (pintype "passive"))
    )
    (net (code "100") (name "unconnected-(U4-VDD_SDIO_NC-Pad26)") (class "Default")
      (node (ref "U4") (pin "26") (pinfunction "VDD_SDIO_NC_26") (pintype "passive"))
    )
    (net (code "101") (name "unconnected-(U4-XTAL_N_NC-Pad44)") (class "Default")
      (node (ref "U4") (pin "44") (pinfunction "XTAL_N_NC_44") (pintype "passive"))
    )
    (net (code "102") (name "unconnected-(U4-XTAL_P_NC-Pad45)") (class "Default")
      (node (ref "U4") (pin "45") (pinfunction "XTAL_P_NC_45") (pintype "passive"))
    )
    (net (code "103") (name "unconnected-(U5-NC-Pad8)") (class "Default")
      (node (ref "U5") (pin "8") (pinfunction "NC_8") (pintype "passive+no_connect"))
    )
    (net (code "104") (name "unconnected-(USB1-RX1+-PadB11)") (class "Default")
      (node (ref "USB1") (pin "B11") (pinfunction "RX1+_B11") (pintype "passive"))
    )
    (net (code "105") (name "unconnected-(USB1-RX1--PadB10)") (class "Default")
      (node (ref "USB1") (pin "B10") (pinfunction "RX1-_B10") (pintype "passive"))
    )
    (net (code "106") (name "unconnected-(USB1-RX2+-PadA11)") (class "Default")
      (node (ref "USB1") (pin "A11") (pinfunction "RX2+_A11") (pintype "passive"))
    )
    (net (code "107") (name "unconnected-(USB1-RX2--PadA10)") (class "Default")
      (node (ref "USB1") (pin "A10") (pinfunction "RX2-_A10") (pintype "passive"))
    )
    (net (code "108") (name "unconnected-(USB1-SBU1-PadA8)") (class "Default")
      (node (ref "USB1") (pin "A8") (pinfunction "SBU1_A8") (pintype "passive"))
    )
    (net (code "109") (name "unconnected-(USB1-SBU2-PadB8)") (class "Default")
      (node (ref "USB1") (pin "B8") (pinfunction "SBU2_B8") (pintype "passive"))
    )
    (net (code "110") (name "unconnected-(USB1-TX1+-PadA2)") (class "Default")
      (node (ref "USB1") (pin "A2") (pinfunction "TX1+_A2") (pintype "passive"))
    )
    (net (code "111") (name "unconnected-(USB1-TX1--PadA3)") (class "Default")
      (node (ref "USB1") (pin "A3") (pinfunction "TX1-_A3") (pintype "passive"))
    )
    (net (code "112") (name "unconnected-(USB1-TX2+-PadB2)") (class "Default")
      (node (ref "USB1") (pin "B2") (pinfunction "TX2+_B2") (pintype "passive"))
    )
    (net (code "113") (name "unconnected-(USB1-TX2--PadB3)") (class "Default")
      (node (ref "USB1") (pin "B3") (pinfunction "TX2-_B3") (pintype "passive"))
    )
  )
)
